# revision2-not-tested.net
KiCad netlist of a schematic drawn in EAGLE
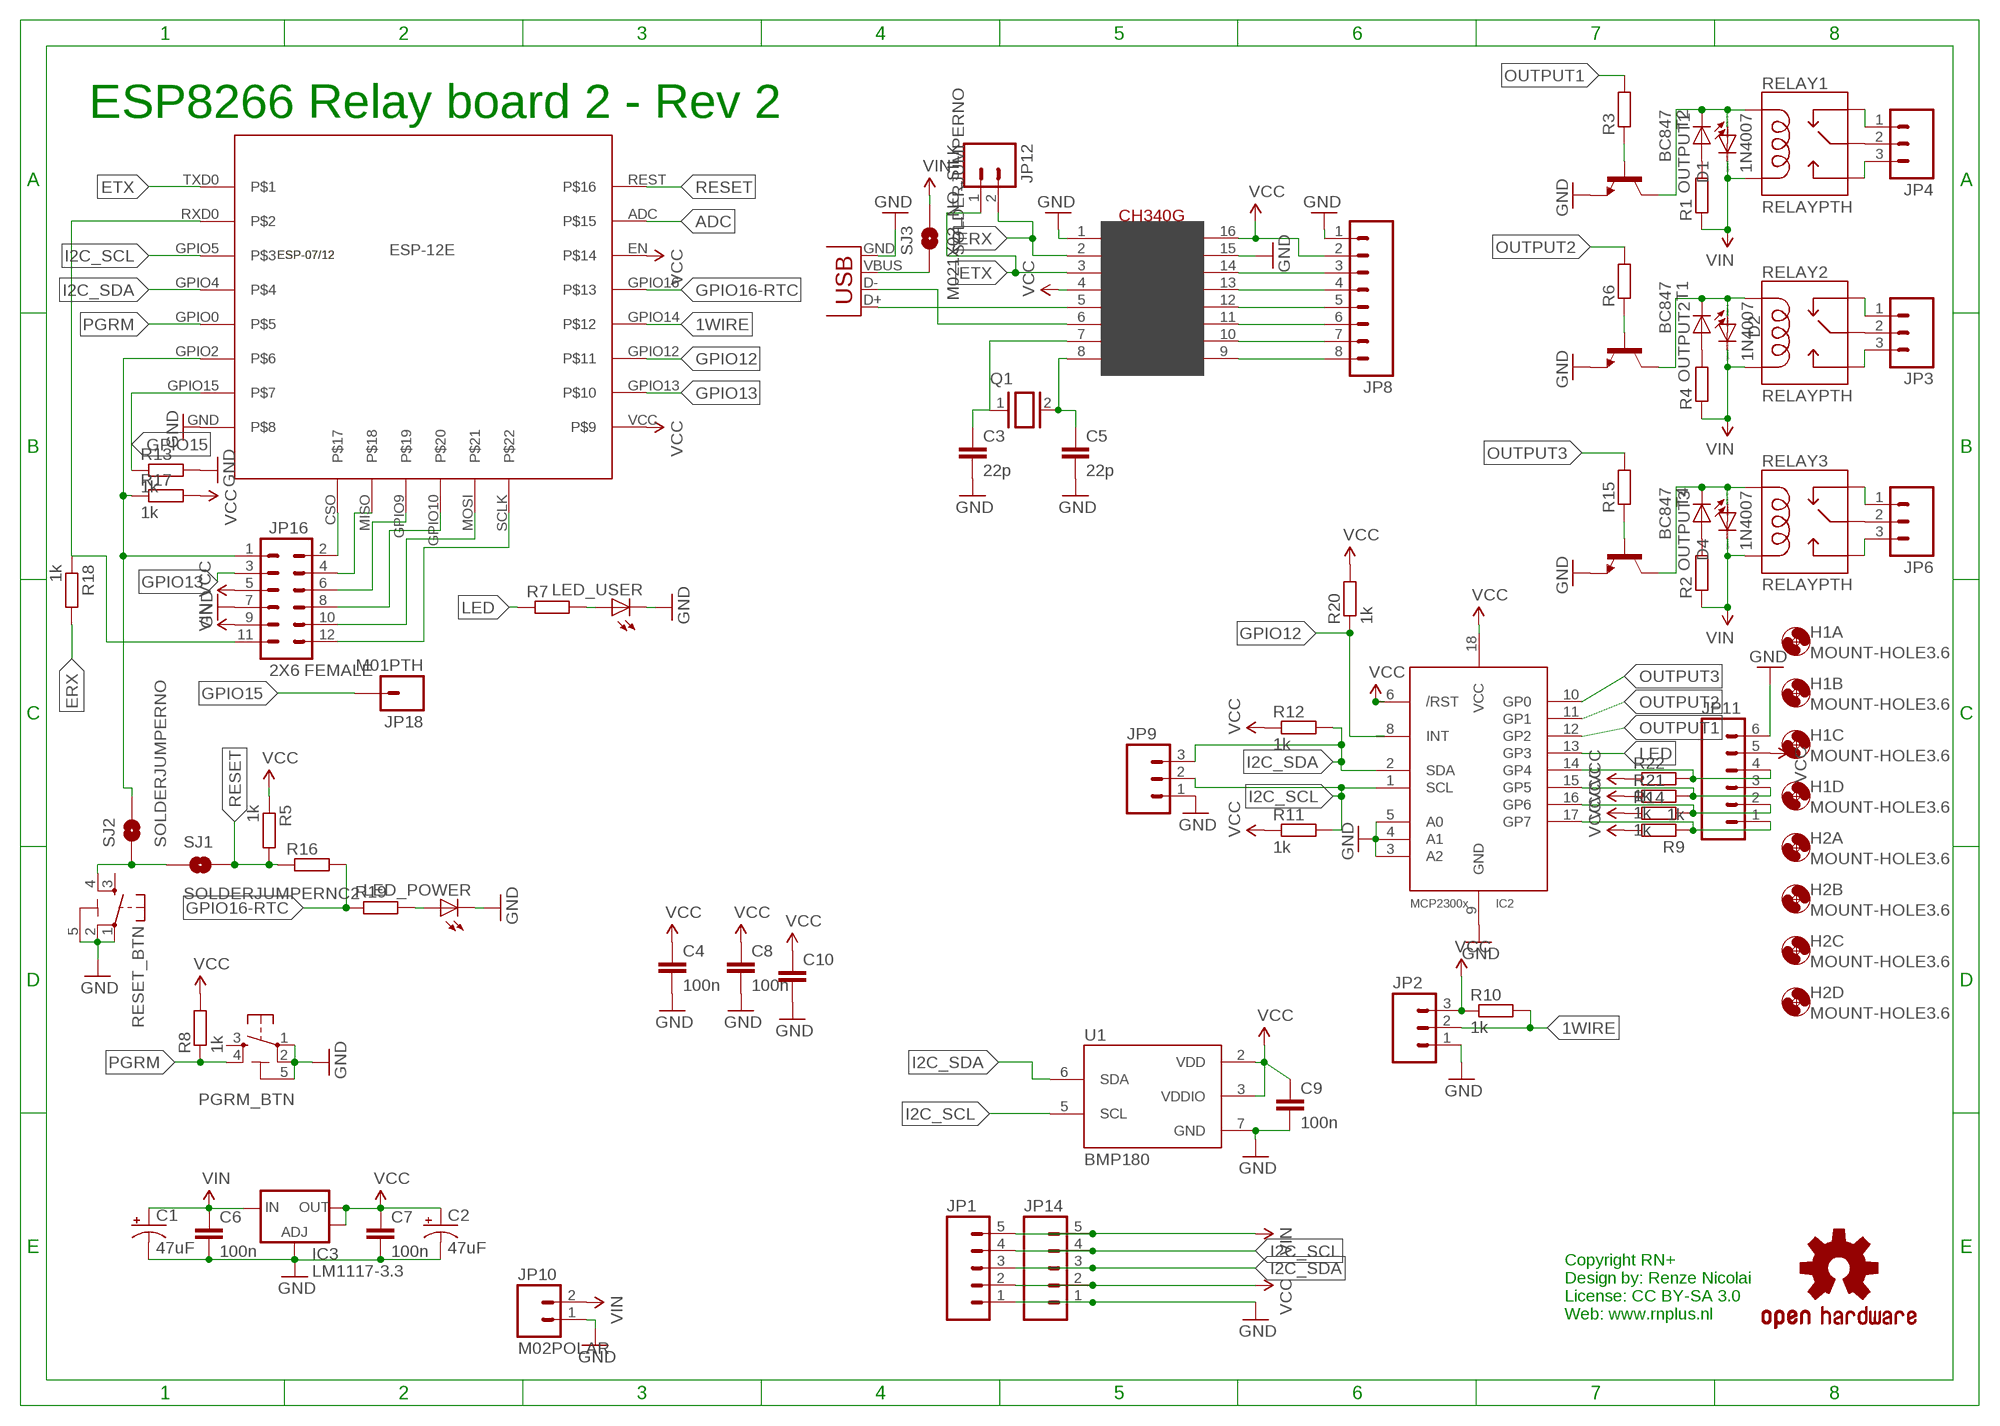
[diagram p0: schematic, sheet 1]

(export (version "E")
  (design (tool "Eeschema 10.0.6"))
  (components
    (comp (ref "C1")
      (value "47uF")
      (footprint "eagle-import:PANASONIC_D")
      (libsource (lib "eagle-import") (part "CAP_POLD"))
    )
    (comp (ref "C2")
      (value "47uF")
      (footprint "eagle-import:PANASONIC_D")
      (libsource (lib "eagle-import") (part "CAP_POLD"))
    )
    (comp (ref "C3")
      (value "22p")
      (footprint "eagle-import:C0805K")
      (libsource (lib "eagle-import") (part "C-EUC0805K"))
    )
    (comp (ref "C4")
      (value "100n")
      (footprint "eagle-import:C0805K")
      (libsource (lib "eagle-import") (part "C-EUC0805K"))
    )
    (comp (ref "C5")
      (value "22p")
      (footprint "eagle-import:C0805K")
      (libsource (lib "eagle-import") (part "C-EUC0805K"))
    )
    (comp (ref "C6")
      (value "100n")
      (footprint "eagle-import:C0805K")
      (libsource (lib "eagle-import") (part "C-EUC0805K"))
    )
    (comp (ref "C7")
      (value "100n")
      (footprint "eagle-import:C0805K")
      (libsource (lib "eagle-import") (part "C-EUC0805K"))
    )
    (comp (ref "C8")
      (value "100n")
      (footprint "eagle-import:C0805K")
      (libsource (lib "eagle-import") (part "C-EUC0805K"))
    )
    (comp (ref "C9")
      (value "100n")
      (footprint "eagle-import:C0805K")
      (libsource (lib "eagle-import") (part "C-EUC0805K"))
    )
    (comp (ref "C10")
      (value "C-EUC0805K")
      (footprint "eagle-import:C0805K")
      (libsource (lib "eagle-import") (part "C-EUC0805K"))
    )
    (comp (ref "D1")
      (value "1N4942")
      (footprint "eagle-import:DO41-10")
      (libsource (lib "eagle-import") (part "1N4942"))
    )
    (comp (ref "D2")
      (value "1N4942")
      (footprint "eagle-import:DO41-10")
      (libsource (lib "eagle-import") (part "1N4942"))
    )
    (comp (ref "D4")
      (value "1N4942")
      (footprint "eagle-import:DO41-10")
      (libsource (lib "eagle-import") (part "1N4942"))
    )
    (comp (ref "H1A")
      (value "MOUNT-HOLE3.6")
      (footprint "eagle-import:3,6")
      (libsource (lib "eagle-import") (part "MOUNT-HOLE3.6"))
    )
    (comp (ref "H1B")
      (value "MOUNT-HOLE3.6")
      (footprint "eagle-import:3,6")
      (libsource (lib "eagle-import") (part "MOUNT-HOLE3.6"))
    )
    (comp (ref "H1C")
      (value "MOUNT-HOLE3.6")
      (footprint "eagle-import:3,6")
      (libsource (lib "eagle-import") (part "MOUNT-HOLE3.6"))
    )
    (comp (ref "H1D")
      (value "MOUNT-HOLE3.6")
      (footprint "eagle-import:3,6")
      (libsource (lib "eagle-import") (part "MOUNT-HOLE3.6"))
    )
    (comp (ref "H2A")
      (value "MOUNT-HOLE3.6")
      (footprint "eagle-import:3,6")
      (libsource (lib "eagle-import") (part "MOUNT-HOLE3.6"))
    )
    (comp (ref "H2B")
      (value "MOUNT-HOLE3.6")
      (footprint "eagle-import:3,6")
      (libsource (lib "eagle-import") (part "MOUNT-HOLE3.6"))
    )
    (comp (ref "H2C")
      (value "MOUNT-HOLE3.6")
      (footprint "eagle-import:3,6")
      (libsource (lib "eagle-import") (part "MOUNT-HOLE3.6"))
    )
    (comp (ref "H2D")
      (value "MOUNT-HOLE3.6")
      (footprint "eagle-import:3,6")
      (libsource (lib "eagle-import") (part "MOUNT-HOLE3.6"))
    )
    (comp (ref "IC2")
      (value "MCP23008/SO")
      (footprint "eagle-import:SO18W")
      (libsource (lib "eagle-import") (part "MCP23008/SO"))
    )
    (comp (ref "IC3")
      (value "LM1117-3.3")
      (footprint "eagle-import:SOT223")
      (libsource (lib "eagle-import") (part "V_REG_LM1117SOT223"))
    )
    (comp (ref "JP1")
      (value "M05PTH")
      (footprint "eagle-import:1X05")
      (libsource (lib "eagle-import") (part "M05PTH"))
    )
    (comp (ref "JP2")
      (value "M03LONGPADS")
      (footprint "eagle-import:1X03_LONGPADS")
      (libsource (lib "eagle-import") (part "M03LONGPADS"))
    )
    (comp (ref "JP3")
      (value "M03-SCREW-5MM")
      (footprint "eagle-import:SCREWTERMINAL-5MM-3")
      (libsource (lib "eagle-import") (part "M03-SCREW-5MM"))
    )
    (comp (ref "JP4")
      (value "M03-SCREW-5MM")
      (footprint "eagle-import:SCREWTERMINAL-5MM-3")
      (libsource (lib "eagle-import") (part "M03-SCREW-5MM"))
    )
    (comp (ref "JP5")
      (value "USB-B")
      (footprint "eagle-import:USB-B-PTH")
      (libsource (lib "eagle-import") (part "USBPTH"))
    )
    (comp (ref "JP6")
      (value "M03-SCREW-5MM")
      (footprint "eagle-import:SCREWTERMINAL-5MM-3")
      (libsource (lib "eagle-import") (part "M03-SCREW-5MM"))
    )
    (comp (ref "JP8")
      (value "M08SILK_FEMALE_PTH")
      (footprint "eagle-import:1X08")
      (libsource (lib "eagle-import") (part "M08SILK_FEMALE_PTH"))
    )
    (comp (ref "JP9")
      (value "M031X03_NO_SILK")
      (footprint "eagle-import:1X03_NO_SILK")
      (libsource (lib "eagle-import") (part "M031X03_NO_SILK"))
    )
    (comp (ref "JP10")
      (value "M02POLAR")
      (footprint "eagle-import:MOLEX-1X2")
      (libsource (lib "eagle-import") (part "M02POLAR"))
    )
    (comp (ref "JP11")
      (value "M06LONGPADS")
      (footprint "eagle-import:1X06_LONGPADS")
      (libsource (lib "eagle-import") (part "M06LONGPADS"))
    )
    (comp (ref "JP12")
      (value "M021X02_NO_SILK")
      (footprint "eagle-import:1X02_NO_SILK")
      (libsource (lib "eagle-import") (part "M021X02_NO_SILK"))
    )
    (comp (ref "JP14")
      (value "M05PTH")
      (footprint "eagle-import:1X05")
      (libsource (lib "eagle-import") (part "M05PTH"))
    )
    (comp (ref "JP16")
      (value "2X6 FEMALE")
      (footprint "eagle-import:2X6")
      (libsource (lib "eagle-import") (part "M06X2PTH_FEMALE"))
    )
    (comp (ref "JP18")
      (value "M01PTH")
      (footprint "eagle-import:1X01")
      (libsource (lib "eagle-import") (part "M01PTH"))
    )
    (comp (ref "LED_POWER")
      (value "LEDCHIP-LED0805")
      (footprint "eagle-import:CHIP-LED0805")
      (libsource (lib "eagle-import") (part "LEDCHIP-LED0805"))
    )
    (comp (ref "LED_USER")
      (value "LEDCHIP-LED0805")
      (footprint "eagle-import:CHIP-LED0805")
      (libsource (lib "eagle-import") (part "LEDCHIP-LED0805"))
    )
    (comp (ref "LOGO1")
      (value "OSHW-LOGOL")
      (footprint "eagle-import:OSHW-LOGO-L")
      (libsource (lib "eagle-import") (part "OSHW-LOGOL"))
    )
    (comp (ref "OUTPUT1")
      (value "LEDCHIP-LED0805")
      (footprint "eagle-import:CHIP-LED0805")
      (libsource (lib "eagle-import") (part "LEDCHIP-LED0805"))
    )
    (comp (ref "OUTPUT2")
      (value "LEDCHIP-LED0805")
      (footprint "eagle-import:CHIP-LED0805")
      (libsource (lib "eagle-import") (part "LEDCHIP-LED0805"))
    )
    (comp (ref "OUTPUT3")
      (value "LEDCHIP-LED0805")
      (footprint "eagle-import:CHIP-LED0805")
      (libsource (lib "eagle-import") (part "LEDCHIP-LED0805"))
    )
    (comp (ref "PGRM_BTN")
      (value "SMARTPRJ_TS42")
      (footprint "eagle-import:SMARTPRJ_TS42")
      (libsource (lib "eagle-import") (part "SMARTPRJ_TS42"))
    )
    (comp (ref "Q1")
      (value "XTAL/S")
      (footprint "eagle-import:QS")
      (libsource (lib "eagle-import") (part "XTAL/S"))
    )
    (comp (ref "R1")
      (value "SMARTPRJ_R-EU_M0805")
      (footprint "eagle-import:SMARTPRJ_M0805")
      (libsource (lib "eagle-import") (part "SMARTPRJ_R-EU_M0805"))
    )
    (comp (ref "R2")
      (value "SMARTPRJ_R-EU_M0805")
      (footprint "eagle-import:SMARTPRJ_M0805")
      (libsource (lib "eagle-import") (part "SMARTPRJ_R-EU_M0805"))
    )
    (comp (ref "R3")
      (value "SMARTPRJ_R-EU_M0805")
      (footprint "eagle-import:SMARTPRJ_M0805")
      (libsource (lib "eagle-import") (part "SMARTPRJ_R-EU_M0805"))
    )
    (comp (ref "R4")
      (value "SMARTPRJ_R-EU_M0805")
      (footprint "eagle-import:SMARTPRJ_M0805")
      (libsource (lib "eagle-import") (part "SMARTPRJ_R-EU_M0805"))
    )
    (comp (ref "R5")
      (value "1k")
      (footprint "eagle-import:SMARTPRJ_M0805")
      (libsource (lib "eagle-import") (part "SMARTPRJ_R-EU_M0805"))
    )
    (comp (ref "R6")
      (value "SMARTPRJ_R-EU_M0805")
      (footprint "eagle-import:SMARTPRJ_M0805")
      (libsource (lib "eagle-import") (part "SMARTPRJ_R-EU_M0805"))
    )
    (comp (ref "R7")
      (value "SMARTPRJ_R-EU_M0805")
      (footprint "eagle-import:SMARTPRJ_M0805")
      (libsource (lib "eagle-import") (part "SMARTPRJ_R-EU_M0805"))
    )
    (comp (ref "R8")
      (value "1k")
      (footprint "eagle-import:SMARTPRJ_M0805")
      (libsource (lib "eagle-import") (part "SMARTPRJ_R-EU_M0805"))
    )
    (comp (ref "R9")
      (value "1k")
      (footprint "eagle-import:SMARTPRJ_M0805")
      (libsource (lib "eagle-import") (part "SMARTPRJ_R-EU_M0805"))
    )
    (comp (ref "R10")
      (value "1k")
      (footprint "eagle-import:SMARTPRJ_M0805")
      (libsource (lib "eagle-import") (part "SMARTPRJ_R-EU_M0805"))
    )
    (comp (ref "R11")
      (value "1k")
      (footprint "eagle-import:SMARTPRJ_M0805")
      (libsource (lib "eagle-import") (part "SMARTPRJ_R-EU_M0805"))
    )
    (comp (ref "R12")
      (value "1k")
      (footprint "eagle-import:SMARTPRJ_M0805")
      (libsource (lib "eagle-import") (part "SMARTPRJ_R-EU_M0805"))
    )
    (comp (ref "R13")
      (value "1k")
      (footprint "eagle-import:SMARTPRJ_M0805")
      (libsource (lib "eagle-import") (part "SMARTPRJ_R-EU_M0805"))
    )
    (comp (ref "R14")
      (value "1k")
      (footprint "eagle-import:SMARTPRJ_M0805")
      (libsource (lib "eagle-import") (part "SMARTPRJ_R-EU_M0805"))
    )
    (comp (ref "R15")
      (value "SMARTPRJ_R-EU_M0805")
      (footprint "eagle-import:SMARTPRJ_M0805")
      (libsource (lib "eagle-import") (part "SMARTPRJ_R-EU_M0805"))
    )
    (comp (ref "R16")
      (value "SMARTPRJ_R-EU_M0805")
      (footprint "eagle-import:SMARTPRJ_M0805")
      (libsource (lib "eagle-import") (part "SMARTPRJ_R-EU_M0805"))
    )
    (comp (ref "R17")
      (value "1k")
      (footprint "eagle-import:SMARTPRJ_M0805")
      (libsource (lib "eagle-import") (part "SMARTPRJ_R-EU_M0805"))
    )
    (comp (ref "R18")
      (value "1k")
      (footprint "eagle-import:SMARTPRJ_M0805")
      (libsource (lib "eagle-import") (part "SMARTPRJ_R-EU_M0805"))
    )
    (comp (ref "R19")
      (value "SMARTPRJ_R-EU_M0805")
      (footprint "eagle-import:SMARTPRJ_M0805")
      (libsource (lib "eagle-import") (part "SMARTPRJ_R-EU_M0805"))
    )
    (comp (ref "R20")
      (value "1k")
      (footprint "eagle-import:SMARTPRJ_M0805")
      (libsource (lib "eagle-import") (part "SMARTPRJ_R-EU_M0805"))
    )
    (comp (ref "R21")
      (value "1k")
      (footprint "eagle-import:SMARTPRJ_M0805")
      (libsource (lib "eagle-import") (part "SMARTPRJ_R-EU_M0805"))
    )
    (comp (ref "R22")
      (value "1k")
      (footprint "eagle-import:SMARTPRJ_M0805")
      (libsource (lib "eagle-import") (part "SMARTPRJ_R-EU_M0805"))
    )
    (comp (ref "RELAY1")
      (value "RELAYPTH")
      (footprint "eagle-import:SRD-05VDC-SL-C")
      (libsource (lib "eagle-import") (part "RELAYPTH"))
    )
    (comp (ref "RELAY2")
      (value "RELAYPTH")
      (footprint "eagle-import:SRD-05VDC-SL-C")
      (libsource (lib "eagle-import") (part "RELAYPTH"))
    )
    (comp (ref "RELAY3")
      (value "RELAYPTH")
      (footprint "eagle-import:SRD-05VDC-SL-C")
      (libsource (lib "eagle-import") (part "RELAYPTH"))
    )
    (comp (ref "RESET_BTN")
      (value "SMARTPRJ_TS42")
      (footprint "eagle-import:SMARTPRJ_TS42")
      (libsource (lib "eagle-import") (part "SMARTPRJ_TS42"))
    )
    (comp (ref "SJ1")
      (value "SOLDERJUMPERNC2")
      (footprint "eagle-import:SJ_2S-NOTRACE")
      (libsource (lib "eagle-import") (part "SOLDERJUMPERNC2"))
    )
    (comp (ref "SJ2")
      (value "SOLDERJUMPERNO")
      (footprint "eagle-import:SJ_2S-NO")
      (libsource (lib "eagle-import") (part "SOLDERJUMPERNO"))
    )
    (comp (ref "SJ3")
      (value "SOLDERJUMPERNO")
      (footprint "eagle-import:SJ_2S-NO")
      (libsource (lib "eagle-import") (part "SOLDERJUMPERNO"))
    )
    (comp (ref "T1")
      (value "BC847")
      (footprint "eagle-import:SOT23")
      (libsource (lib "eagle-import") (part "BC847"))
    )
    (comp (ref "T2")
      (value "BC847")
      (footprint "eagle-import:SOT23")
      (libsource (lib "eagle-import") (part "BC847"))
    )
    (comp (ref "T4")
      (value "BC847")
      (footprint "eagle-import:SOT23")
      (libsource (lib "eagle-import") (part "BC847"))
    )
    (comp (ref "U$1")
      (value "CH340G")
      (footprint "eagle-import:SOIC16")
      (libsource (lib "eagle-import") (part "CH340G"))
    )
    (comp (ref "U$2")
      (value "ESP-07/12_ESP-12E")
      (footprint "eagle-import:ESP-07_12")
      (libsource (lib "eagle-import") (part "ESP-07/12_ESP-12E"))
    )
    (comp (ref "U1")
      (value "BMP180")
      (footprint "eagle-import:BMP180")
      (libsource (lib "eagle-import") (part "BMP180"))
    )
  )
  (nets
    (net (code "1") (name "1WIRE") (class "Default")
      (node (ref "JP2") (pin "2") (pinfunction "2_2") (pintype "passive"))
      (node (ref "R10") (pin "2") (pinfunction "2_2") (pintype "passive"))
      (node (ref "U$2") (pin "GPIO14") (pinfunction "P$12_GPIO14") (pintype "bidirectional"))
    )
    (net (code "2") (name "ADC") (class "Default")
      (node (ref "U$2") (pin "ADC") (pinfunction "P$15_ADC") (pintype "bidirectional"))
    )
    (net (code "3") (name "ERX") (class "Default")
      (node (ref "JP12") (pin "2") (pinfunction "2_2") (pintype "passive"))
      (node (ref "R18") (pin "2") (pinfunction "2_2") (pintype "passive"))
      (node (ref "U$1") (pin "2") (pinfunction "TX_2") (pintype "bidirectional"))
    )
    (net (code "4") (name "ETX") (class "Default")
      (node (ref "JP12") (pin "1") (pinfunction "1_1") (pintype "passive"))
      (node (ref "U$1") (pin "3") (pinfunction "RX_3") (pintype "bidirectional"))
      (node (ref "U$2") (pin "TXD0") (pinfunction "P$1_TXD0") (pintype "bidirectional"))
    )
    (net (code "5") (name "GND") (class "Default")
      (node (ref "C1") (pin "-") (pinfunction "-_-") (pintype "passive"))
      (node (ref "C10") (pin "2") (pinfunction "2_2") (pintype "passive"))
      (node (ref "C2") (pin "-") (pinfunction "-_-") (pintype "passive"))
      (node (ref "C3") (pin "2") (pinfunction "2_2") (pintype "passive"))
      (node (ref "C4") (pin "2") (pinfunction "2_2") (pintype "passive"))
      (node (ref "C5") (pin "2") (pinfunction "2_2") (pintype "passive"))
      (node (ref "C6") (pin "2") (pinfunction "2_2") (pintype "passive"))
      (node (ref "C7") (pin "2") (pinfunction "2_2") (pintype "passive"))
      (node (ref "C8") (pin "2") (pinfunction "2_2") (pintype "passive"))
      (node (ref "C9") (pin "2") (pinfunction "2_2") (pintype "passive"))
      (node (ref "IC2") (pin "3") (pinfunction "A2_3") (pintype "input"))
      (node (ref "IC2") (pin "4") (pinfunction "A1_4") (pintype "input"))
      (node (ref "IC2") (pin "5") (pinfunction "A0_5") (pintype "input"))
      (node (ref "IC2") (pin "9") (pinfunction "GND_9") (pintype "power_in"))
      (node (ref "IC3") (pin "1") (pinfunction "ADJ_1") (pintype "input"))
      (node (ref "JP1") (pin "1") (pinfunction "1_1") (pintype "passive"))
      (node (ref "JP10") (pin "1") (pinfunction "1_1") (pintype "passive"))
      (node (ref "JP11") (pin "6") (pinfunction "6_6") (pintype "passive"))
      (node (ref "JP14") (pin "1") (pinfunction "1_1") (pintype "passive"))
      (node (ref "JP16") (pin "7") (pinfunction "7_7") (pintype "passive"))
      (node (ref "JP2") (pin "1") (pinfunction "1_1") (pintype "passive"))
      (node (ref "JP5") (pin "GND") (pinfunction "GND_GND") (pintype "bidirectional"))
      (node (ref "JP8") (pin "1") (pinfunction "1_1") (pintype "passive"))
      (node (ref "JP9") (pin "1") (pinfunction "1_1") (pintype "passive"))
      (node (ref "LED_POWER") (pin "C") (pinfunction "C_C") (pintype "passive"))
      (node (ref "LED_USER") (pin "C") (pinfunction "C_C") (pintype "passive"))
      (node (ref "PGRM_BTN") (pin "1") (pinfunction "1_1") (pintype "passive"))
      (node (ref "PGRM_BTN") (pin "2") (pinfunction "2_2") (pintype "passive"))
      (node (ref "PGRM_BTN") (pin "5") (pinfunction "5-GND_5") (pintype "power_in"))
      (node (ref "R13") (pin "2") (pinfunction "2_2") (pintype "passive"))
      (node (ref "RESET_BTN") (pin "1") (pinfunction "1_1") (pintype "passive"))
      (node (ref "RESET_BTN") (pin "2") (pinfunction "2_2") (pintype "passive"))
      (node (ref "RESET_BTN") (pin "5") (pinfunction "5-GND_5") (pintype "power_in"))
      (node (ref "T1") (pin "2") (pinfunction "E_2") (pintype "passive"))
      (node (ref "T2") (pin "2") (pinfunction "E_2") (pintype "passive"))
      (node (ref "T4") (pin "2") (pinfunction "E_2") (pintype "passive"))
      (node (ref "U$1") (pin "1") (pinfunction "GND_1") (pintype "bidirectional"))
      (node (ref "U$1") (pin "15") (pinfunction "RS232_15") (pintype "bidirectional"))
      (node (ref "U$2") (pin "GND") (pinfunction "P$8_GND") (pintype "bidirectional"))
      (node (ref "U1") (pin "7") (pinfunction "GND_7") (pintype "power_in"))
    )
    (net (code "6") (name "GPIO12") (class "Default")
      (node (ref "IC2") (pin "8") (pinfunction "INT_8") (pintype "output"))
      (node (ref "R20") (pin "1") (pinfunction "1_1") (pintype "passive"))
      (node (ref "U$2") (pin "GPIO12") (pinfunction "P$11_GPIO12") (pintype "bidirectional"))
    )
    (net (code "7") (name "GPIO13") (class "Default")
      (node (ref "JP16") (pin "3") (pinfunction "3_3") (pintype "passive"))
      (node (ref "U$2") (pin "GPIO13") (pinfunction "P$10_GPIO13") (pintype "bidirectional"))
    )
    (net (code "8") (name "GPIO15") (class "Default")
      (node (ref "JP18") (pin "1") (pinfunction "1_1") (pintype "passive"))
      (node (ref "R13") (pin "1") (pinfunction "1_1") (pintype "passive"))
      (node (ref "U$2") (pin "GPIO15") (pinfunction "P$7_GPIO15") (pintype "bidirectional"))
    )
    (net (code "9") (name "GPIO16-RTC") (class "Default")
      (node (ref "R16") (pin "2") (pinfunction "2_2") (pintype "passive"))
      (node (ref "R19") (pin "1") (pinfunction "1_1") (pintype "passive"))
      (node (ref "U$2") (pin "GPIO16") (pinfunction "P$13_GPIO16") (pintype "bidirectional"))
    )
    (net (code "10") (name "I2C_SCL") (class "Default")
      (node (ref "IC2") (pin "1") (pinfunction "SCL_1") (pintype "bidirectional"))
      (node (ref "JP1") (pin "4") (pinfunction "4_4") (pintype "passive"))
      (node (ref "JP14") (pin "4") (pinfunction "4_4") (pintype "passive"))
      (node (ref "JP9") (pin "2") (pinfunction "2_2") (pintype "passive"))
      (node (ref "R11") (pin "2") (pinfunction "2_2") (pintype "passive"))
      (node (ref "U$2") (pin "GPIO5") (pinfunction "P$3_GPIO5") (pintype "bidirectional"))
      (node (ref "U1") (pin "5") (pinfunction "SCL_5") (pintype "input"))
    )
    (net (code "11") (name "I2C_SDA") (class "Default")
      (node (ref "IC2") (pin "2") (pinfunction "SDA_2") (pintype "bidirectional"))
      (node (ref "JP1") (pin "3") (pinfunction "3_3") (pintype "passive"))
      (node (ref "JP14") (pin "3") (pinfunction "3_3") (pintype "passive"))
      (node (ref "JP9") (pin "3") (pinfunction "3_3") (pintype "passive"))
      (node (ref "R12") (pin "2") (pinfunction "2_2") (pintype "passive"))
      (node (ref "U$2") (pin "GPIO4") (pinfunction "P$4_GPIO4") (pintype "bidirectional"))
      (node (ref "U1") (pin "6") (pinfunction "SDA_6") (pintype "bidirectional"))
    )
    (net (code "12") (name "LED") (class "Default")
      (node (ref "IC2") (pin "13") (pinfunction "GP3_13") (pintype "bidirectional"))
      (node (ref "R7") (pin "1") (pinfunction "1_1") (pintype "passive"))
    )
    (net (code "13") (name "Net-(IC2-GP4)") (class "Default")
      (node (ref "IC2") (pin "14") (pinfunction "GP4_14") (pintype "bidirectional"))
      (node (ref "JP11") (pin "4") (pinfunction "4_4") (pintype "passive"))
      (node (ref "R22") (pin "2") (pinfunction "2_2") (pintype "passive"))
    )
    (net (code "14") (name "Net-(IC2-GP5)") (class "Default")
      (node (ref "IC2") (pin "15") (pinfunction "GP5_15") (pintype "bidirectional"))
      (node (ref "JP11") (pin "3") (pinfunction "3_3") (pintype "passive"))
      (node (ref "R21") (pin "2") (pinfunction "2_2") (pintype "passive"))
    )
    (net (code "15") (name "Net-(IC2-GP6)") (class "Default")
      (node (ref "IC2") (pin "16") (pinfunction "GP6_16") (pintype "bidirectional"))
      (node (ref "JP11") (pin "2") (pinfunction "2_2") (pintype "passive"))
      (node (ref "R14") (pin "2") (pinfunction "2_2") (pintype "passive"))
    )
    (net (code "16") (name "Net-(IC2-GP7)") (class "Default")
      (node (ref "IC2") (pin "17") (pinfunction "GP7_17") (pintype "bidirectional"))
      (node (ref "JP11") (pin "1") (pinfunction "1_1") (pintype "passive"))
      (node (ref "R9") (pin "1") (pinfunction "1_1") (pintype "passive"))
    )
    (net (code "17") (name "Net-(JP3-Pad2)") (class "Default")
      (node (ref "JP3") (pin "2") (pinfunction "2_2") (pintype "passive"))
      (node (ref "RELAY2") (pin "SWCOMMON") (pinfunction "SWCOMMON_SWCOMMON") (pintype "bidirectional"))
    )
    (net (code "18") (name "Net-(JP3-Pad3)") (class "Default")
      (node (ref "JP3") (pin "3") (pinfunction "3_3") (pintype "passive"))
      (node (ref "RELAY2") (pin "SWOPEN") (pinfunction "SWOPEN_SWOPEN") (pintype "bidirectional"))
    )
    (net (code "19") (name "Net-(JP4-Pad2)") (class "Default")
      (node (ref "JP4") (pin "2") (pinfunction "2_2") (pintype "passive"))
      (node (ref "RELAY1") (pin "SWCOMMON") (pinfunction "SWCOMMON_SWCOMMON") (pintype "bidirectional"))
    )
    (net (code "20") (name "Net-(JP4-Pad3)") (class "Default")
      (node (ref "JP4") (pin "3") (pinfunction "3_3") (pintype "passive"))
      (node (ref "RELAY1") (pin "SWOPEN") (pinfunction "SWOPEN_SWOPEN") (pintype "bidirectional"))
    )
    (net (code "21") (name "Net-(JP5-PadVBUS)") (class "Default")
      (node (ref "JP5") (pin "VBUS") (pinfunction "VBUS_VBUS") (pintype "bidirectional"))
      (node (ref "SJ3") (pin "1") (pinfunction "1_1") (pintype "passive"))
    )
    (net (code "22") (name "Net-(JP6-Pad2)") (class "Default")
      (node (ref "JP6") (pin "2") (pinfunction "2_2") (pintype "passive"))
      (node (ref "RELAY3") (pin "SWCOMMON") (pinfunction "SWCOMMON_SWCOMMON") (pintype "bidirectional"))
    )
    (net (code "23") (name "Net-(JP6-Pad3)") (class "Default")
      (node (ref "JP6") (pin "3") (pinfunction "3_3") (pintype "passive"))
      (node (ref "RELAY3") (pin "SWOPEN") (pinfunction "SWOPEN_SWOPEN") (pintype "bidirectional"))
    )
    (net (code "24") (name "Net-(LED_POWER-PadA)") (class "Default")
      (node (ref "LED_POWER") (pin "A") (pinfunction "A_A") (pintype "passive"))
      (node (ref "R19") (pin "2") (pinfunction "2_2") (pintype "passive"))
    )
    (net (code "25") (name "Net-(LED_USER-PadA)") (class "Default")
      (node (ref "LED_USER") (pin "A") (pinfunction "A_A") (pintype "passive"))
      (node (ref "R7") (pin "2") (pinfunction "2_2") (pintype "passive"))
    )
    (net (code "26") (name "Net-(OUTPUT1-PadA)") (class "Default")
      (node (ref "OUTPUT1") (pin "A") (pinfunction "A_A") (pintype "passive"))
      (node (ref "R1") (pin "2") (pinfunction "2_2") (pintype "passive"))
    )
    (net (code "27") (name "Net-(OUTPUT2-PadA)") (class "Default")
      (node (ref "OUTPUT2") (pin "A") (pinfunction "A_A") (pintype "passive"))
      (node (ref "R4") (pin "2") (pinfunction "2_2") (pintype "passive"))
    )
    (net (code "28") (name "Net-(OUTPUT3-PadA)") (class "Default")
      (node (ref "OUTPUT3") (pin "A") (pinfunction "A_A") (pintype "passive"))
      (node (ref "R2") (pin "2") (pinfunction "2_2") (pintype "passive"))
    )
    (net (code "29") (name "Net-(RELAY1-SWCLOSE)") (class "Default")
      (node (ref "JP4") (pin "1") (pinfunction "1_1") (pintype "passive"))
      (node (ref "RELAY1") (pin "SWCLOSED") (pinfunction "SWCLOSE_SWCLOSED") (pintype "bidirectional"))
    )
    (net (code "30") (name "Net-(RELAY2-SWCLOSE)") (class "Default")
      (node (ref "JP3") (pin "1") (pinfunction "1_1") (pintype "passive"))
      (node (ref "RELAY2") (pin "SWCLOSED") (pinfunction "SWCLOSE_SWCLOSED") (pintype "bidirectional"))
    )
    (net (code "31") (name "Net-(RELAY3-SWCLOSE)") (class "Default")
      (node (ref "JP6") (pin "1") (pinfunction "1_1") (pintype "passive"))
      (node (ref "RELAY3") (pin "SWCLOSED") (pinfunction "SWCLOSE_SWCLOSED") (pintype "bidirectional"))
    )
    (net (code "32") (name "Net-(RESET_BTN-Pad4)") (class "Default")
      (node (ref "RESET_BTN") (pin "4") (pinfunction "4_4") (pintype "passive"))
      (node (ref "SJ1") (pin "1") (pinfunction "1_1") (pintype "passive"))
      (node (ref "SJ2") (pin "1") (pinfunction "1_1") (pintype "passive"))
    )
    (net (code "33") (name "Net-(T1-B)") (class "Default")
      (node (ref "R6") (pin "1") (pinfunction "1_1") (pintype "passive"))
      (node (ref "T1") (pin "1") (pinfunction "B_1") (pintype "passive"))
    )
    (net (code "34") (name "Net-(T1-C)") (class "Default")
      (node (ref "D2") (pin "A") (pinfunction "A_A") (pintype "passive"))
      (node (ref "OUTPUT2") (pin "C") (pinfunction "C_C") (pintype "passive"))
      (node (ref "RELAY2") (pin "COIL1") (pinfunction "COIL1_COIL1") (pintype "bidirectional"))
      (node (ref "T1") (pin "3") (pinfunction "C_3") (pintype "passive"))
    )
    (net (code "35") (name "Net-(T2-B)") (class "Default")
      (node (ref "R3") (pin "1") (pinfunction "1_1") (pintype "passive"))
      (node (ref "T2") (pin "1") (pinfunction "B_1") (pintype "passive"))
    )
    (net (code "36") (name "Net-(T2-C)") (class "Default")
      (node (ref "D1") (pin "A") (pinfunction "A_A") (pintype "passive"))
      (node (ref "OUTPUT1") (pin "C") (pinfunction "C_C") (pintype "passive"))
      (node (ref "RELAY1") (pin "COIL1") (pinfunction "COIL1_COIL1") (pintype "bidirectional"))
      (node (ref "T2") (pin "3") (pinfunction "C_3") (pintype "passive"))
    )
    (net (code "37") (name "Net-(T4-B)") (class "Default")
      (node (ref "R15") (pin "1") (pinfunction "1_1") (pintype "passive"))
      (node (ref "T4") (pin "1") (pinfunction "B_1") (pintype "passive"))
    )
    (net (code "38") (name "Net-(T4-C)") (class "Default")
      (node (ref "D4") (pin "A") (pinfunction "A_A") (pintype "passive"))
      (node (ref "OUTPUT3") (pin "C") (pinfunction "C_C") (pintype "passive"))
      (node (ref "RELAY3") (pin "COIL1") (pinfunction "COIL1_COIL1") (pintype "bidirectional"))
      (node (ref "T4") (pin "3") (pinfunction "C_3") (pintype "passive"))
    )
    (net (code "39") (name "Net-(U$1-CTS)") (class "Default")
      (node (ref "JP8") (pin "8") (pinfunction "8_8") (pintype "passive"))
      (node (ref "U$1") (pin "9") (pinfunction "CTS_9") (pintype "bidirectional"))
    )
    (net (code "40") (name "Net-(U$1-D+)") (class "Default")
      (node (ref "JP5") (pin "D+") (pinfunction "D+_D+") (pintype "bidirectional"))
      (node (ref "U$1") (pin "5") (pinfunction "D+_5") (pintype "bidirectional"))
    )
    (net (code "41") (name "Net-(U$1-D-)") (class "Default")
      (node (ref "JP5") (pin "D-") (pinfunction "D-_D-") (pintype "bidirectional"))
      (node (ref "U$1") (pin "6") (pinfunction "D-_6") (pintype "bidirectional"))
    )
    (net (code "42") (name "Net-(U$1-DCD)") (class "Default")
      (node (ref "JP8") (pin "5") (pinfunction "5_5") (pintype "passive"))
      (node (ref "U$1") (pin "12") (pinfunction "DCD_12") (pintype "bidirectional"))
    )
    (net (code "43") (name "Net-(U$1-DSR)") (class "Default")
      (node (ref "JP8") (pin "7") (pinfunction "7_7") (pintype "passive"))
      (node (ref "U$1") (pin "10") (pinfunction "DSR_10") (pintype "bidirectional"))
    )
    (net (code "44") (name "Net-(U$1-DTR)") (class "Default")
      (node (ref "JP8") (pin "4") (pinfunction "4_4") (pintype "passive"))
      (node (ref "U$1") (pin "13") (pinfunction "DTR_13") (pintype "bidirectional"))
    )
    (net (code "45") (name "Net-(U$1-RI)") (class "Default")
      (node (ref "JP8") (pin "6") (pinfunction "6_6") (pintype "passive"))
      (node (ref "U$1") (pin "11") (pinfunction "RI_11") (pintype "bidirectional"))
    )
    (net (code "46") (name "Net-(U$1-RTS)") (class "Default")
      (node (ref "JP8") (pin "3") (pinfunction "3_3") (pintype "passive"))
      (node (ref "U$1") (pin "14") (pinfunction "RTS_14") (pintype "bidirectional"))
    )
    (net (code "47") (name "Net-(U$1-XI)") (class "Default")
      (node (ref "C3") (pin "1") (pinfunction "1_1") (pintype "passive"))
      (node (ref "Q1") (pin "1") (pinfunction "1_1") (pintype "passive"))
      (node (ref "U$1") (pin "7") (pinfunction "XI_7") (pintype "bidirectional"))
    )
    (net (code "48") (name "Net-(U$1-XO)") (class "Default")
      (node (ref "C5") (pin "1") (pinfunction "1_1") (pintype "passive"))
      (node (ref "Q1") (pin "2") (pinfunction "2_2") (pintype "passive"))
      (node (ref "U$1") (pin "8") (pinfunction "XO_8") (pintype "bidirectional"))
    )
    (net (code "49") (name "Net-(U$2-P$2)") (class "Default")
      (node (ref "JP16") (pin "11") (pinfunction "11_11") (pintype "passive"))
      (node (ref "R18") (pin "1") (pinfunction "1_1") (pintype "passive"))
      (node (ref "U$2") (pin "RXD0") (pinfunction "P$2_RXD0") (pintype "bidirectional"))
    )
    (net (code "50") (name "Net-(U$2-P$6)") (class "Default")
      (node (ref "JP16") (pin "1") (pinfunction "1_1") (pintype "passive"))
      (node (ref "R17") (pin "1") (pinfunction "1_1") (pintype "passive"))
      (node (ref "SJ2") (pin "2") (pinfunction "2_2") (pintype "passive"))
      (node (ref "U$2") (pin "GPIO2") (pinfunction "P$6_GPIO2") (pintype "bidirectional"))
    )
    (net (code "51") (name "Net-(U$2-P$17)") (class "Default")
      (node (ref "JP16") (pin "2") (pinfunction "2_2") (pintype "passive"))
      (node (ref "U$2") (pin "CSO") (pinfunction "P$17_CSO") (pintype "bidirectional"))
    )
    (net (code "52") (name "Net-(U$2-P$18)") (class "Default")
      (node (ref "JP16") (pin "4") (pinfunction "4_4") (pintype "passive"))
      (node (ref "U$2") (pin "MISO") (pinfunction "P$18_MISO") (pintype "bidirectional"))
    )
    (net (code "53") (name "Net-(U$2-P$19)") (class "Default")
      (node (ref "JP16") (pin "6") (pinfunction "6_6") (pintype "passive"))
      (node (ref "U$2") (pin "GPIO9") (pinfunction "P$19_GPIO9") (pintype "bidirectional"))
    )
    (net (code "54") (name "Net-(U$2-P$20)") (class "Default")
      (node (ref "JP16") (pin "8") (pinfunction "8_8") (pintype "passive"))
      (node (ref "U$2") (pin "GPIO10") (pinfunction "P$20_GPIO10") (pintype "bidirectional"))
    )
    (net (code "55") (name "Net-(U$2-P$21)") (class "Default")
      (node (ref "JP16") (pin "10") (pinfunction "10_10") (pintype "passive"))
      (node (ref "U$2") (pin "MOSI") (pinfunction "P$21_MOSI") (pintype "bidirectional"))
    )
    (net (code "56") (name "Net-(U$2-P$22)") (class "Default")
      (node (ref "JP16") (pin "12") (pinfunction "12_12") (pintype "passive"))
      (node (ref "U$2") (pin "SCLK") (pinfunction "P$22_SCLK") (pintype "bidirectional"))
    )
    (net (code "57") (name "OUTPUT1") (class "Default")
      (node (ref "IC2") (pin "12") (pinfunction "GP2_12") (pintype "bidirectional"))
      (node (ref "R3") (pin "2") (pinfunction "2_2") (pintype "passive"))
    )
    (net (code "58") (name "OUTPUT2") (class "Default")
      (node (ref "IC2") (pin "11") (pinfunction "GP1_11") (pintype "bidirectional"))
      (node (ref "R6") (pin "2") (pinfunction "2_2") (pintype "passive"))
    )
    (net (code "59") (name "OUTPUT3") (class "Default")
      (node (ref "IC2") (pin "10") (pinfunction "GP0_10") (pintype "bidirectional"))
      (node (ref "R15") (pin "2") (pinfunction "2_2") (pintype "passive"))
    )
    (net (code "60") (name "PGRM") (class "Default")
      (node (ref "PGRM_BTN") (pin "4") (pinfunction "4_4") (pintype "passive"))
      (node (ref "R8") (pin "1") (pinfunction "1_1") (pintype "passive"))
      (node (ref "U$2") (pin "GPIO0") (pinfunction "P$5_GPIO0") (pintype "bidirectional"))
    )
    (net (code "61") (name "RESET") (class "Default")
      (node (ref "R16") (pin "1") (pinfunction "1_1") (pintype "passive"))
      (node (ref "R5") (pin "2") (pinfunction "2_2") (pintype "passive"))
      (node (ref "SJ1") (pin "2") (pinfunction "2_2") (pintype "passive"))
      (node (ref "U$2") (pin "REST") (pinfunction "P$16_REST") (pintype "bidirectional"))
    )
    (net (code "62") (name "VCC") (class "Default")
      (node (ref "C10") (pin "1") (pinfunction "1_1") (pintype "passive"))
      (node (ref "C2") (pin "+") (pinfunction "+_+") (pintype "passive"))
      (node (ref "C4") (pin "1") (pinfunction "1_1") (pintype "passive"))
      (node (ref "C7") (pin "1") (pinfunction "1_1") (pintype "passive"))
      (node (ref "C8") (pin "1") (pinfunction "1_1") (pintype "passive"))
      (node (ref "C9") (pin "1") (pinfunction "1_1") (pintype "passive"))
      (node (ref "IC2") (pin "18") (pinfunction "VCC_18") (pintype "power_in"))
      (node (ref "IC2") (pin "6") (pinfunction "/RST_6") (pintype "input"))
      (node (ref "IC3") (pin "2") (pinfunction "OUT_2") (pintype "output"))
      (node (ref "IC3") (pin "4") (pinfunction "OUT_4") (pintype "output"))
      (node (ref "JP1") (pin "2") (pinfunction "2_2") (pintype "passive"))
      (node (ref "JP11") (pin "5") (pinfunction "5_5") (pintype "passive"))
      (node (ref "JP14") (pin "2") (pinfunction "2_2") (pintype "passive"))
      (node (ref "JP16") (pin "5") (pinfunction "5_5") (pintype "passive"))
      (node (ref "JP2") (pin "3") (pinfunction "3_3") (pintype "passive"))
      (node (ref "JP8") (pin "2") (pinfunction "2_2") (pintype "passive"))
      (node (ref "R10") (pin "1") (pinfunction "1_1") (pintype "passive"))
      (node (ref "R11") (pin "1") (pinfunction "1_1") (pintype "passive"))
      (node (ref "R12") (pin "1") (pinfunction "1_1") (pintype "passive"))
      (node (ref "R14") (pin "1") (pinfunction "1_1") (pintype "passive"))
      (node (ref "R17") (pin "2") (pinfunction "2_2") (pintype "passive"))
      (node (ref "R20") (pin "2") (pinfunction "2_2") (pintype "passive"))
      (node (ref "R21") (pin "1") (pinfunction "1_1") (pintype "passive"))
      (node (ref "R22") (pin "1") (pinfunction "1_1") (pintype "passive"))
      (node (ref "R5") (pin "1") (pinfunction "1_1") (pintype "passive"))
      (node (ref "R8") (pin "2") (pinfunction "2_2") (pintype "passive"))
      (node (ref "R9") (pin "2") (pinfunction "2_2") (pintype "passive"))
      (node (ref "U$1") (pin "16") (pinfunction "VCC_16") (pintype "bidirectional"))
      (node (ref "U$1") (pin "4") (pinfunction "V3_4") (pintype "bidirectional"))
      (node (ref "U$2") (pin "EN") (pinfunction "P$14_EN") (pintype "bidirectional"))
      (node (ref "U$2") (pin "VCC") (pinfunction "P$9_VCC") (pintype "bidirectional"))
      (node (ref "U1") (pin "2") (pinfunction "VDD_2") (pintype "power_in"))
      (node (ref "U1") (pin "3") (pinfunction "VDDIO_3") (pintype "power_in"))
    )
    (net (code "63") (name "VIN") (class "Default")
      (node (ref "C1") (pin "+") (pinfunction "+_+") (pintype "passive"))
      (node (ref "C6") (pin "1") (pinfunction "1_1") (pintype "passive"))
      (node (ref "D1") (pin "C") (pinfunction "C_C") (pintype "passive"))
      (node (ref "D2") (pin "C") (pinfunction "C_C") (pintype "passive"))
      (node (ref "D4") (pin "C") (pinfunction "C_C") (pintype "passive"))
      (node (ref "IC3") (pin "3") (pinfunction "IN_3") (pintype "input"))
      (node (ref "JP1") (pin "5") (pinfunction "5_5") (pintype "passive"))
      (node (ref "JP10") (pin "2") (pinfunction "2_2") (pintype "passive"))
      (node (ref "JP14") (pin "5") (pinfunction "5_5") (pintype "passive"))
      (node (ref "JP16") (pin "9") (pinfunction "9_9") (pintype "passive"))
      (node (ref "R1") (pin "1") (pinfunction "1_1") (pintype "passive"))
      (node (ref "R2") (pin "1") (pinfunction "1_1") (pintype "passive"))
      (node (ref "R4") (pin "1") (pinfunction "1_1") (pintype "passive"))
      (node (ref "RELAY1") (pin "COIL0") (pinfunction "COIL0_COIL0") (pintype "bidirectional"))
      (node (ref "RELAY2") (pin "COIL0") (pinfunction "COIL0_COIL0") (pintype "bidirectional"))
      (node (ref "RELAY3") (pin "COIL0") (pinfunction "COIL0_COIL0") (pintype "bidirectional"))
      (node (ref "SJ3") (pin "2") (pinfunction "2_2") (pintype "passive"))
    )
    (net (code "64") (name "unconnected-(PGRM_BTN-Pad3)") (class "Default")
      (node (ref "PGRM_BTN") (pin "3") (pinfunction "3_3") (pintype "passive"))
    )
    (net (code "65") (name "unconnected-(RESET_BTN-Pad3)") (class "Default")
      (node (ref "RESET_BTN") (pin "3") (pinfunction "3_3") (pintype "passive"))
    )
  )
)
